# full_tds.net
KiCad netlist of a schematic drawn in EAGLE
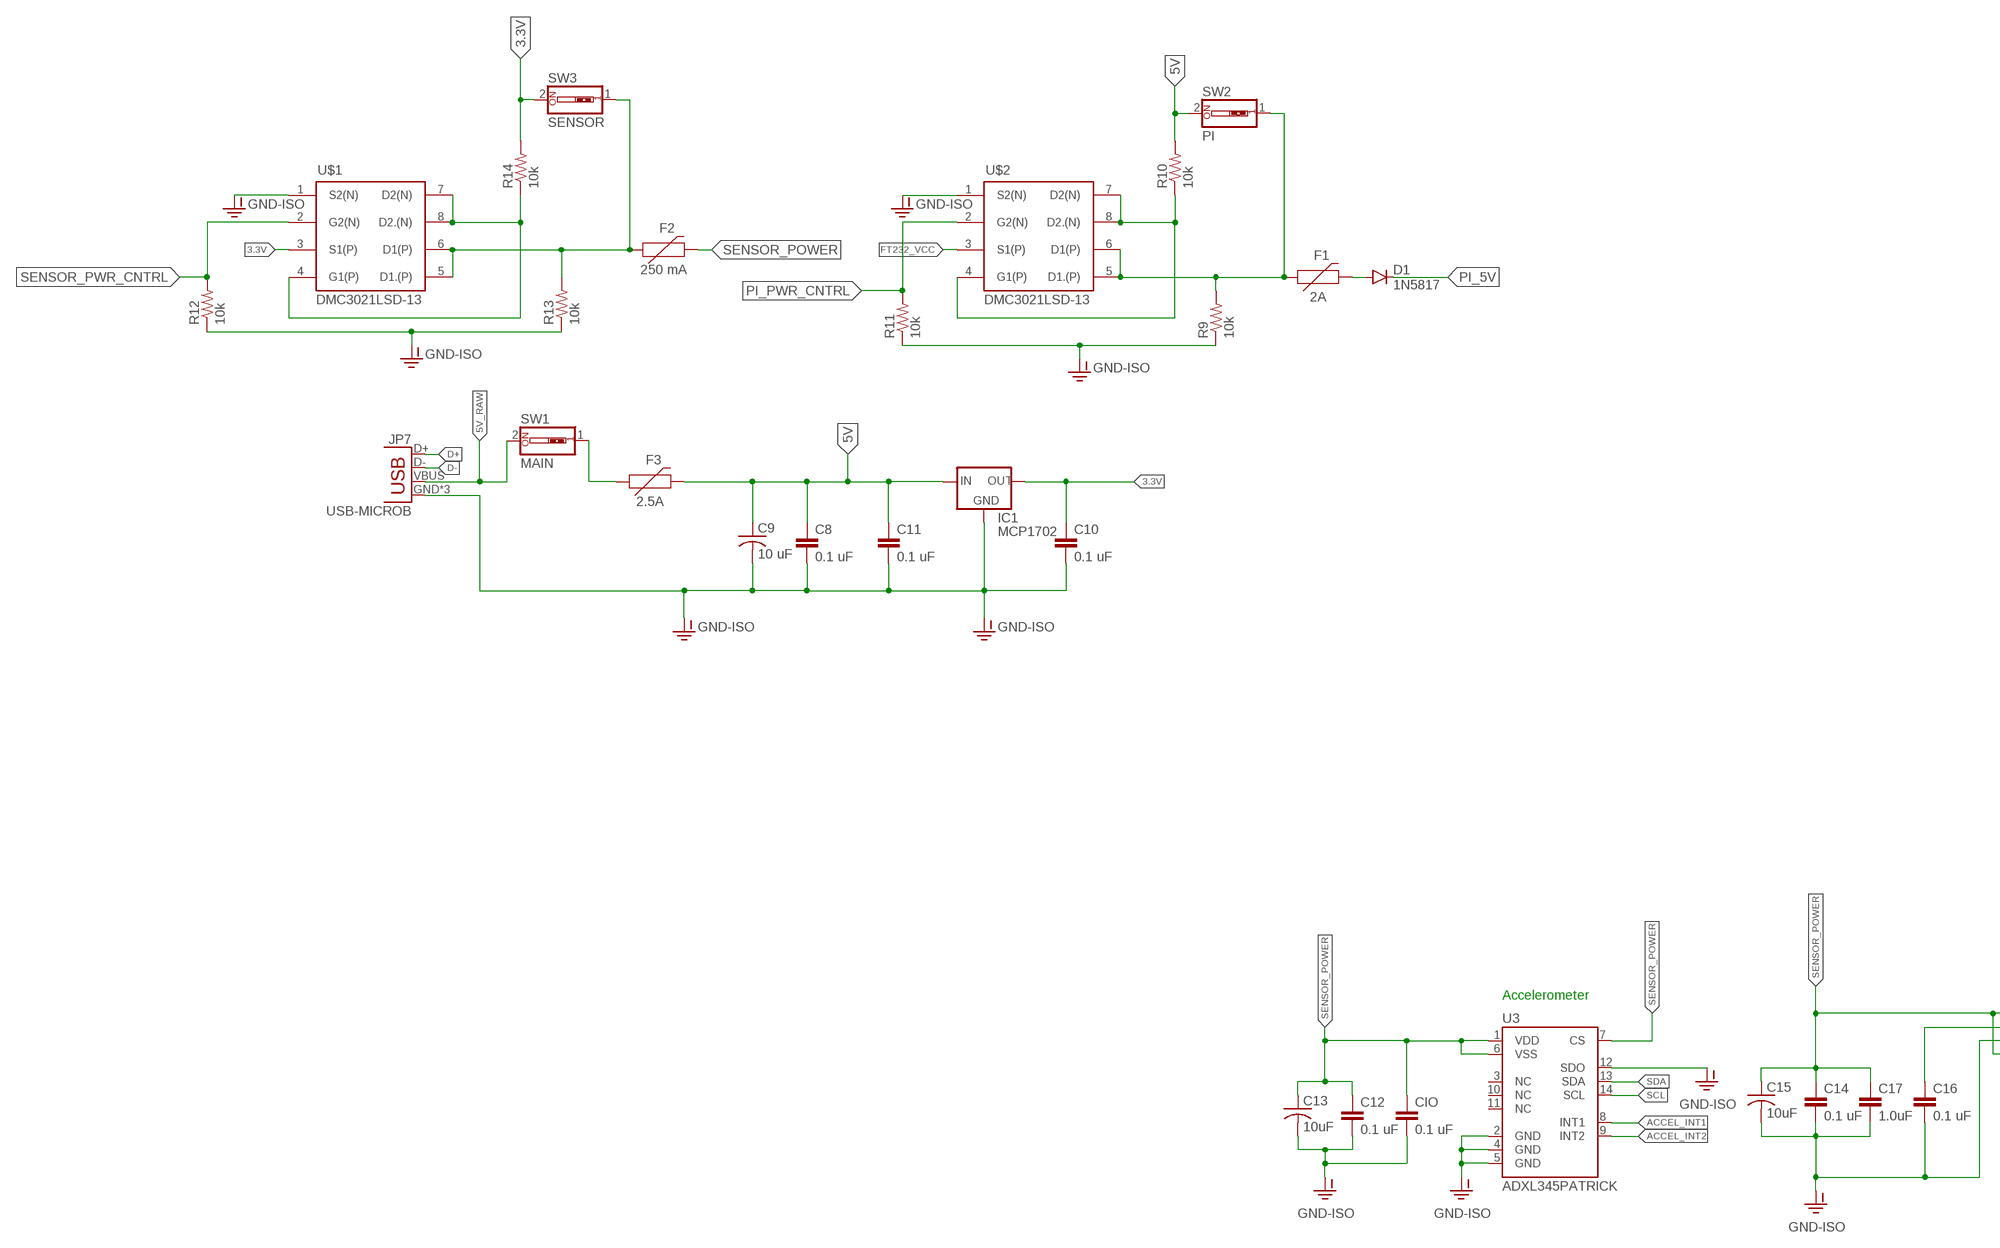
[diagram p0: schematic, sheet 1, part 1 of 2]
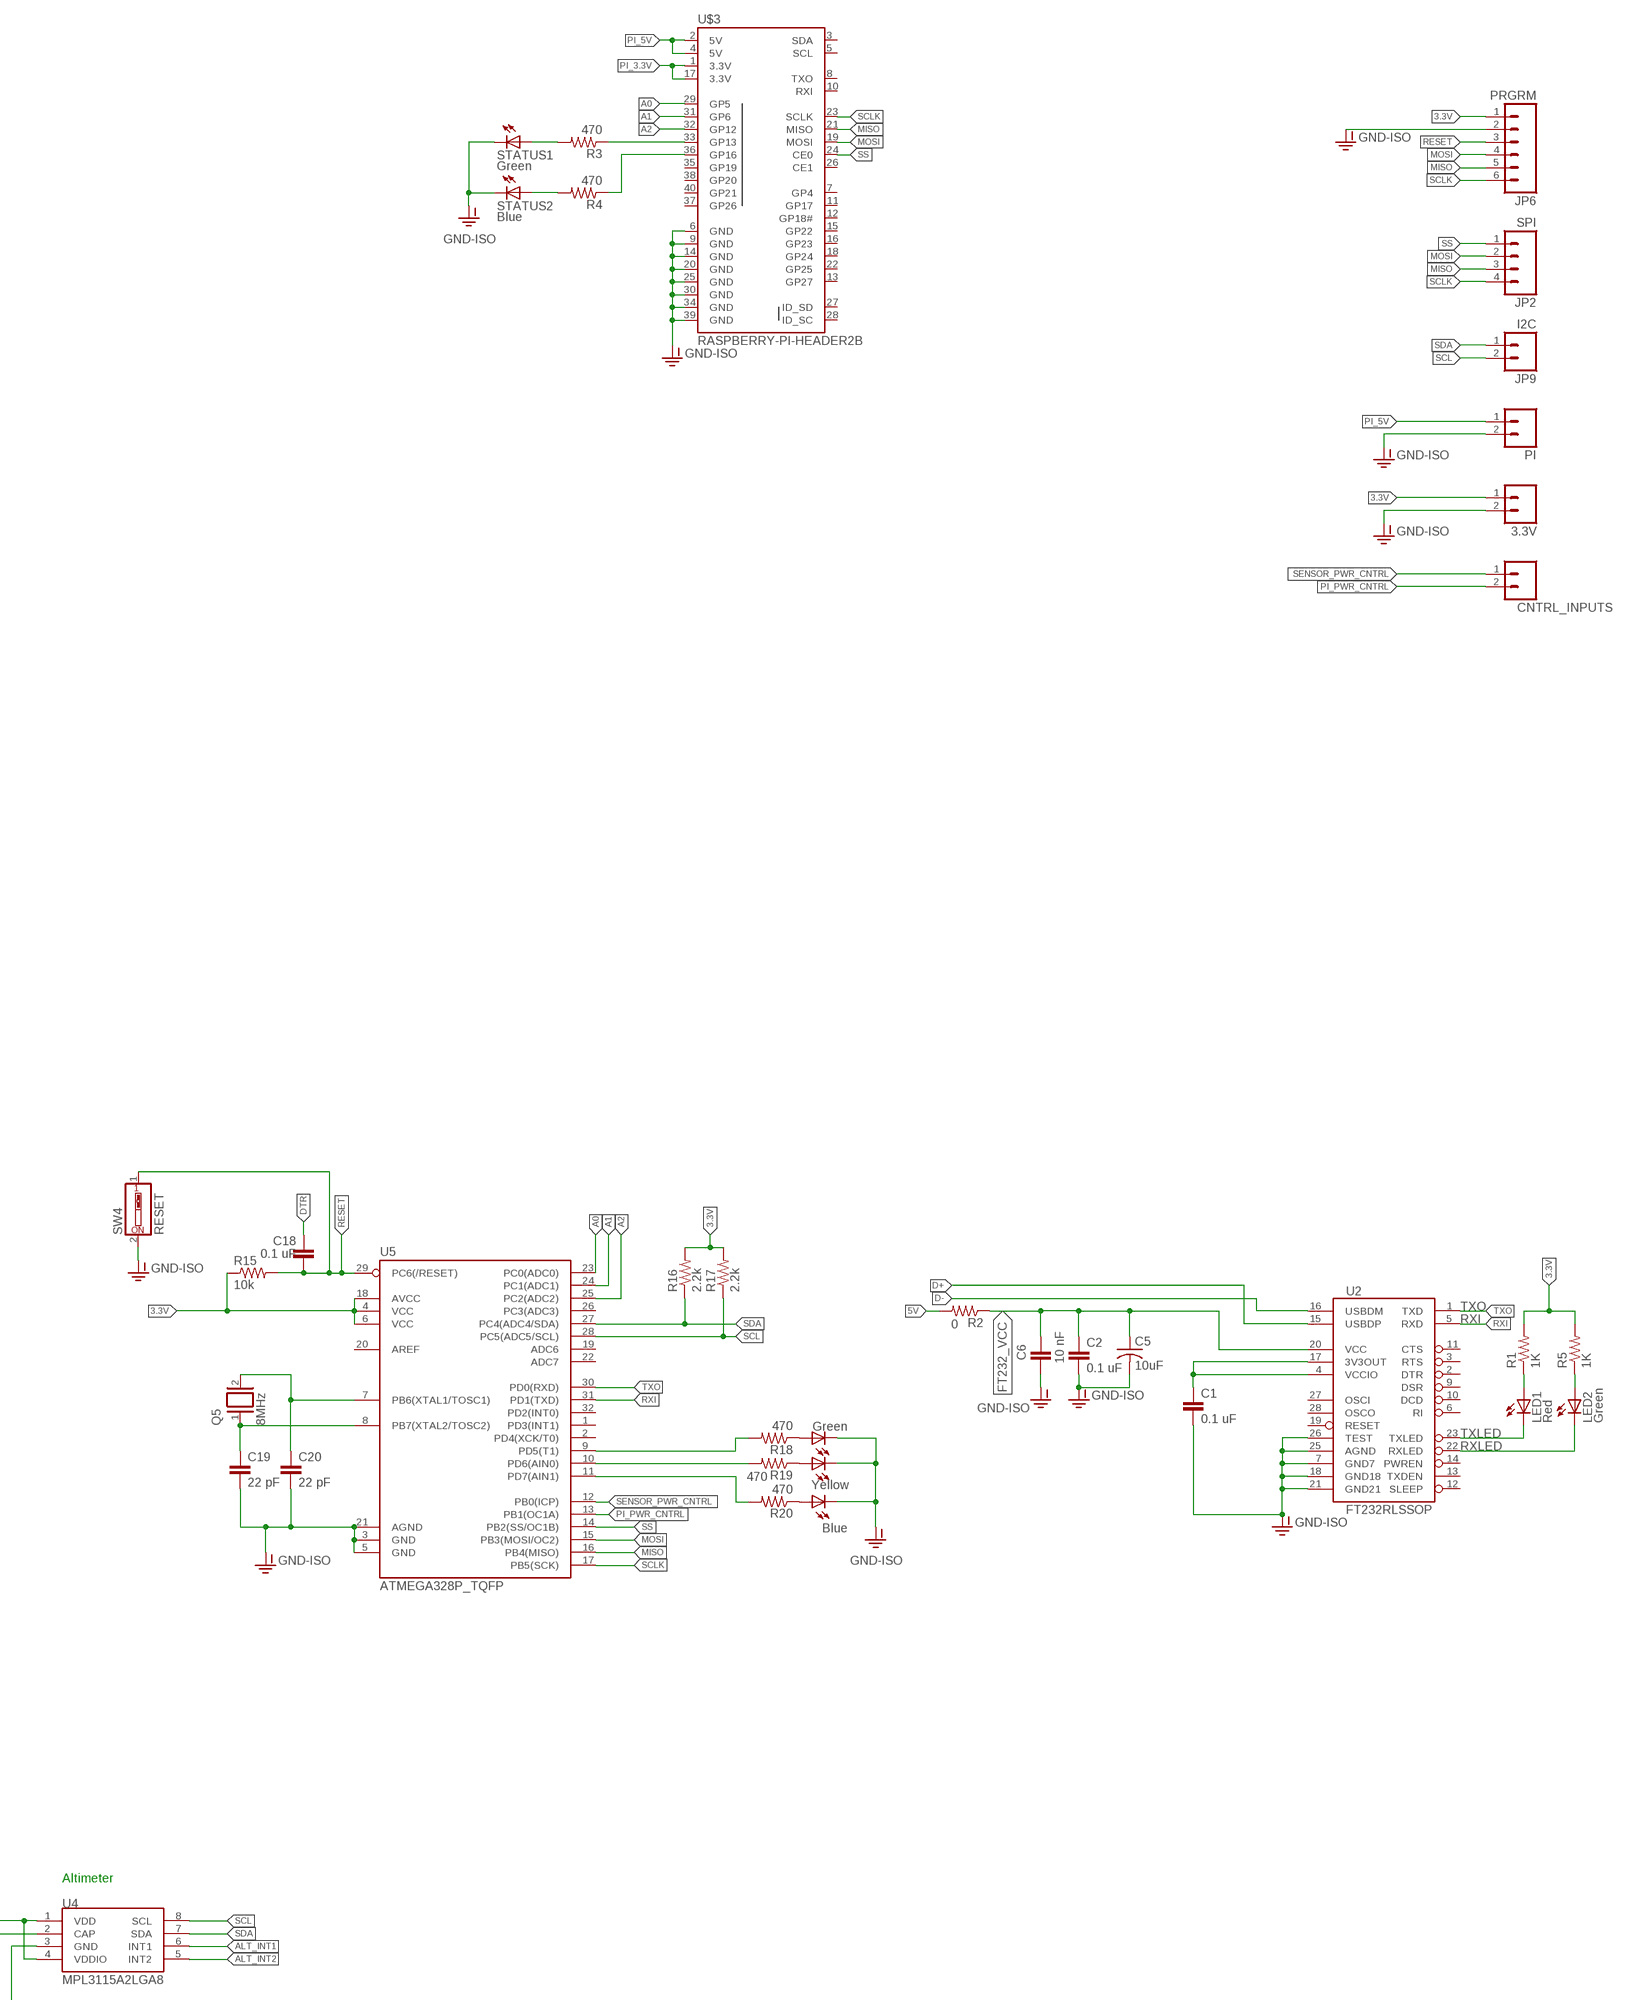
[diagram p1: schematic, sheet 1, part 2 of 2]

(export (version "E")
  (design (tool "Eeschema 10.0.6"))
  (components
    (comp (ref "3.3V")
      (value "M02PTH")
      (footprint "eagle-import:1X02")
      (libsource (lib "eagle-import") (part "M02PTH"))
    )
    (comp (ref "C1")
      (value "0.1 uF")
      (footprint "eagle-import:1206")
      (libsource (lib "eagle-import") (part "1.0UF-1206-50V-10%"))
    )
    (comp (ref "C2")
      (value "0.1 uF")
      (footprint "eagle-import:1206")
      (libsource (lib "eagle-import") (part "1.0UF-1206-50V-10%"))
    )
    (comp (ref "C5")
      (value "10uF")
      (footprint "eagle-import:C1206")
      (libsource (lib "eagle-import") (part "C-USC1206"))
    )
    (comp (ref "C6")
      (value "10 nF")
      (footprint "eagle-import:1206")
      (libsource (lib "eagle-import") (part "1.0UF-1206-50V-10%"))
    )
    (comp (ref "C8")
      (value "0.1 uF")
      (footprint "eagle-import:1206")
      (libsource (lib "eagle-import") (part "1.0UF-1206-50V-10%"))
    )
    (comp (ref "C9")
      (value "10 uF")
      (footprint "eagle-import:C1206")
      (libsource (lib "eagle-import") (part "C-USC1206"))
    )
    (comp (ref "C10")
      (value "0.1 uF")
      (footprint "eagle-import:1206")
      (libsource (lib "eagle-import") (part "1.0UF-1206-50V-10%"))
    )
    (comp (ref "C11")
      (value "0.1 uF")
      (footprint "eagle-import:1206")
      (libsource (lib "eagle-import") (part "1.0UF-1206-50V-10%"))
    )
    (comp (ref "C12")
      (value "0.1 uF")
      (footprint "eagle-import:1206")
      (libsource (lib "eagle-import") (part "1.0UF-1206-50V-10%"))
    )
    (comp (ref "C13")
      (value "10uF")
      (footprint "eagle-import:C1206")
      (libsource (lib "eagle-import") (part "C-USC1206"))
    )
    (comp (ref "C14")
      (value "0.1 uF")
      (footprint "eagle-import:1206")
      (libsource (lib "eagle-import") (part "1.0UF-1206-50V-10%"))
    )
    (comp (ref "C15")
      (value "10uF")
      (footprint "eagle-import:C1206")
      (libsource (lib "eagle-import") (part "C-USC1206"))
    )
    (comp (ref "C16")
      (value "0.1 uF")
      (footprint "eagle-import:1206")
      (libsource (lib "eagle-import") (part "1.0UF-1206-50V-10%"))
    )
    (comp (ref "C17")
      (value "1.0uF")
      (footprint "eagle-import:1206")
      (libsource (lib "eagle-import") (part "1.0UF-1206-50V-10%"))
    )
    (comp (ref "C18")
      (value "0.1 uF")
      (footprint "eagle-import:1206")
      (libsource (lib "eagle-import") (part "1.0UF-1206-50V-10%"))
    )
    (comp (ref "C19")
      (value "22 pF")
      (footprint "eagle-import:1206")
      (libsource (lib "eagle-import") (part "1.0UF-1206-50V-10%"))
    )
    (comp (ref "C20")
      (value "22 pF")
      (footprint "eagle-import:1206")
      (libsource (lib "eagle-import") (part "1.0UF-1206-50V-10%"))
    )
    (comp (ref "CIO")
      (value "0.1 uF")
      (footprint "eagle-import:1206")
      (libsource (lib "eagle-import") (part "1.0UF-1206-50V-10%"))
    )
    (comp (ref "CNTRL_INPUTS")
      (value "M02PTH")
      (footprint "eagle-import:1X02")
      (libsource (lib "eagle-import") (part "M02PTH"))
    )
    (comp (ref "D1")
      (value "1N5817")
      (footprint "eagle-import:DIODE-1N4001")
      (libsource (lib "eagle-import") (part "DIODEPTH"))
    )
    (comp (ref "F1")
      (value "2A")
      (footprint "eagle-import:1206")
      (libsource (lib "eagle-import") (part "PPTC_HALF-AMP"))
    )
    (comp (ref "F2")
      (value "250 mA")
      (footprint "eagle-import:1206")
      (libsource (lib "eagle-import") (part "PPTC_HALF-AMP"))
    )
    (comp (ref "F3")
      (value "2.5A")
      (footprint "eagle-import:1206")
      (libsource (lib "eagle-import") (part "PPTC_HALF-AMP"))
    )
    (comp (ref "IC1")
      (value "MCP1702")
      (footprint "eagle-import:TO92")
      (libsource (lib "eagle-import") (part "MCP1700TRI"))
    )
    (comp (ref "JP2")
      (value "SPI")
      (footprint "eagle-import:1X04")
      (libsource (lib "eagle-import") (part "M04PTH"))
    )
    (comp (ref "JP6")
      (value "PRGRM")
      (footprint "eagle-import:1X06")
      (libsource (lib "eagle-import") (part "M06SILK_FEMALE_PTH"))
    )
    (comp (ref "JP7")
      (value "USB-MICROB")
      (footprint "eagle-import:USB-MICROB")
      (libsource (lib "eagle-import") (part "USB-MICROB"))
    )
    (comp (ref "JP9")
      (value "I2C")
      (footprint "eagle-import:1X02")
      (libsource (lib "eagle-import") (part "M02PTH"))
    )
    (comp (ref "LED1")
      (value "Red")
      (footprint "eagle-import:CHIPLED_1206")
      (libsource (lib "eagle-import") (part "LEDCHIPLED_1206"))
    )
    (comp (ref "LED2")
      (value "Green")
      (footprint "eagle-import:CHIPLED_1206")
      (libsource (lib "eagle-import") (part "LEDCHIPLED_1206"))
    )
    (comp (ref "LED6")
      (value "Green")
      (footprint "eagle-import:CHIPLED_1206")
      (libsource (lib "eagle-import") (part "LEDCHIPLED_1206"))
    )
    (comp (ref "LED7")
      (value "Yellow")
      (footprint "eagle-import:CHIPLED_1206")
      (libsource (lib "eagle-import") (part "LEDCHIPLED_1206"))
    )
    (comp (ref "LED8")
      (value "Blue")
      (footprint "eagle-import:CHIPLED_1206")
      (libsource (lib "eagle-import") (part "LEDCHIPLED_1206"))
    )
    (comp (ref "PI")
      (value "M02PTH")
      (footprint "eagle-import:1X02")
      (libsource (lib "eagle-import") (part "M02PTH"))
    )
    (comp (ref "Q5")
      (value "8MHz")
      (footprint "eagle-import:QS")
      (libsource (lib "eagle-import") (part "XTAL/S"))
    )
    (comp (ref "R1")
      (value "1K")
      (footprint "eagle-import:1206")
      (libsource (lib "eagle-import") (part "SparkFun-Resistors_RESISTOR1206"))
    )
    (comp (ref "R2")
      (value "0")
      (footprint "eagle-import:1206")
      (libsource (lib "eagle-import") (part "SparkFun-Resistors_RESISTOR1206"))
    )
    (comp (ref "R3")
      (value "470")
      (footprint "eagle-import:1206")
      (libsource (lib "eagle-import") (part "RESISTOR1206"))
    )
    (comp (ref "R4")
      (value "470")
      (footprint "eagle-import:1206")
      (libsource (lib "eagle-import") (part "RESISTOR1206"))
    )
    (comp (ref "R5")
      (value "1K")
      (footprint "eagle-import:1206")
      (libsource (lib "eagle-import") (part "SparkFun-Resistors_RESISTOR1206"))
    )
    (comp (ref "R9")
      (value "10k")
      (footprint "eagle-import:R1206")
      (libsource (lib "eagle-import") (part "R-US_R1206"))
    )
    (comp (ref "R10")
      (value "10k")
      (footprint "eagle-import:R1206")
      (libsource (lib "eagle-import") (part "R-US_R1206"))
    )
    (comp (ref "R11")
      (value "10k")
      (footprint "eagle-import:R1206")
      (libsource (lib "eagle-import") (part "R-US_R1206"))
    )
    (comp (ref "R12")
      (value "10k")
      (footprint "eagle-import:R1206")
      (libsource (lib "eagle-import") (part "R-US_R1206"))
    )
    (comp (ref "R13")
      (value "10k")
      (footprint "eagle-import:R1206")
      (libsource (lib "eagle-import") (part "R-US_R1206"))
    )
    (comp (ref "R14")
      (value "10k")
      (footprint "eagle-import:R1206")
      (libsource (lib "eagle-import") (part "R-US_R1206"))
    )
    (comp (ref "R15")
      (value "10k")
      (footprint "eagle-import:1206")
      (libsource (lib "eagle-import") (part "RESISTOR1206"))
    )
    (comp (ref "R16")
      (value "2.2k")
      (footprint "eagle-import:1206")
      (libsource (lib "eagle-import") (part "RESISTOR1206"))
    )
    (comp (ref "R17")
      (value "2.2k")
      (footprint "eagle-import:1206")
      (libsource (lib "eagle-import") (part "RESISTOR1206"))
    )
    (comp (ref "R18")
      (value "470")
      (footprint "eagle-import:1206")
      (libsource (lib "eagle-import") (part "RESISTOR1206"))
    )
    (comp (ref "R19")
      (value "470")
      (footprint "eagle-import:1206")
      (libsource (lib "eagle-import") (part "RESISTOR1206"))
    )
    (comp (ref "R20")
      (value "470")
      (footprint "eagle-import:1206")
      (libsource (lib "eagle-import") (part "RESISTOR1206"))
    )
    (comp (ref "STATUS1")
      (value "Green")
      (footprint "eagle-import:CHIPLED_1206")
      (libsource (lib "eagle-import") (part "LEDCHIPLED_1206"))
    )
    (comp (ref "STATUS2")
      (value "Blue")
      (footprint "eagle-import:CHIPLED_1206")
      (libsource (lib "eagle-import") (part "LEDCHIPLED_1206"))
    )
    (comp (ref "SW1")
      (value "MAIN")
      (footprint "eagle-import:EDG-01")
      (libsource (lib "eagle-import") (part "SW_DIP-1"))
    )
    (comp (ref "SW2")
      (value "PI")
      (footprint "eagle-import:EDG-01")
      (libsource (lib "eagle-import") (part "SW_DIP-1"))
    )
    (comp (ref "SW3")
      (value "SENSOR")
      (footprint "eagle-import:EDG-01")
      (libsource (lib "eagle-import") (part "SW_DIP-1"))
    )
    (comp (ref "SW4")
      (value "RESET")
      (footprint "eagle-import:EDG-01")
      (libsource (lib "eagle-import") (part "SW_DIP-1"))
    )
    (comp (ref "U$1")
      (value "DMC3021LSD-13")
      (footprint "eagle-import:SOIC-8")
      (libsource (lib "eagle-import") (part "DMC3021LSD-13"))
    )
    (comp (ref "U$2")
      (value "DMC3021LSD-13")
      (footprint "eagle-import:SOIC-8")
      (libsource (lib "eagle-import") (part "DMC3021LSD-13"))
    )
    (comp (ref "U$3")
      (value "RASPBERRY-PI-HEADER2B")
      (footprint "eagle-import:2X20-NOSILK")
      (libsource (lib "eagle-import") (part "RASPBERRY-PI-HEADER2B"))
    )
    (comp (ref "U2")
      (value "FT232RLSSOP")
      (footprint "eagle-import:SSOP28DB")
      (libsource (lib "eagle-import") (part "FT232RLSSOP"))
    )
    (comp (ref "U3")
      (value "ADXL345PATRICK")
      (footprint "eagle-import:LGA14_1_1_PATRICK")
      (libsource (lib "eagle-import") (part "ADXL345PATRICK"))
    )
    (comp (ref "U4")
      (value "MPL3115A2LGA8")
      (footprint "eagle-import:LGA8")
      (libsource (lib "eagle-import") (part "MPL3115A2LGA8"))
    )
    (comp (ref "U5")
      (value "ATMEGA328P_TQFP")
      (footprint "eagle-import:TQFP32-08")
      (libsource (lib "eagle-import") (part "ATMEGA328P_TQFP"))
    )
  )
  (nets
    (net (code "1") (name "/RXLED") (class "Default")
      (node (ref "LED2") (pin "C") (pinfunction "C_C") (pintype "passive"))
      (node (ref "U2") (pin "22") (pinfunction "RXLED_22") (pintype "input"))
    )
    (net (code "2") (name "/TXLED") (class "Default")
      (node (ref "LED1") (pin "C") (pinfunction "C_C") (pintype "passive"))
      (node (ref "U2") (pin "23") (pinfunction "TXLED_23") (pintype "input"))
    )
    (net (code "3") (name "3.3V") (class "Default")
      (node (ref "3.3V") (pin "1") (pinfunction "1_1") (pintype "passive"))
      (node (ref "C10") (pin "1") (pinfunction "1_1") (pintype "passive"))
      (node (ref "IC1") (pin "3") (pinfunction "OUT_3") (pintype "passive"))
      (node (ref "JP6") (pin "1") (pinfunction "1_1") (pintype "passive"))
      (node (ref "R1") (pin "2") (pinfunction "2_2") (pintype "passive"))
      (node (ref "R14") (pin "2") (pinfunction "2_2") (pintype "passive"))
      (node (ref "R15") (pin "1") (pinfunction "1_1") (pintype "passive"))
      (node (ref "R16") (pin "2") (pinfunction "2_2") (pintype "passive"))
      (node (ref "R17") (pin "2") (pinfunction "2_2") (pintype "passive"))
      (node (ref "R5") (pin "2") (pinfunction "2_2") (pintype "passive"))
      (node (ref "SW3") (pin "2") (pinfunction "2_2") (pintype "passive"))
      (node (ref "U$1") (pin "3") (pinfunction "S1(P)_3") (pintype "bidirectional"))
      (node (ref "U5") (pin "18") (pinfunction "AVCC_18") (pintype "bidirectional"))
      (node (ref "U5") (pin "4") (pinfunction "VCC_4") (pintype "bidirectional"))
      (node (ref "U5") (pin "6") (pinfunction "VCC_6") (pintype "bidirectional"))
    )
    (net (code "4") (name "5V") (class "Default")
      (node (ref "C11") (pin "1") (pinfunction "1_1") (pintype "passive"))
      (node (ref "C8") (pin "1") (pinfunction "1_1") (pintype "passive"))
      (node (ref "C9") (pin "1") (pinfunction "1_1") (pintype "passive"))
      (node (ref "F3") (pin "2") (pinfunction "2_2") (pintype "bidirectional"))
      (node (ref "IC1") (pin "2") (pinfunction "IN_2") (pintype "input"))
      (node (ref "R10") (pin "2") (pinfunction "2_2") (pintype "passive"))
      (node (ref "R2") (pin "2") (pinfunction "2_2") (pintype "passive"))
      (node (ref "SW2") (pin "2") (pinfunction "2_2") (pintype "passive"))
    )
    (net (code "5") (name "5V_RAW") (class "Default")
      (node (ref "JP7") (pin "VBUS") (pinfunction "VBUS_VBUS") (pintype "bidirectional"))
      (node (ref "SW1") (pin "2") (pinfunction "2_2") (pintype "passive"))
    )
    (net (code "6") (name "A0") (class "Default")
      (node (ref "U$3") (pin "29") (pinfunction "GP5_29") (pintype "bidirectional"))
      (node (ref "U5") (pin "23") (pinfunction "PC0(ADC0)_23") (pintype "bidirectional"))
    )
    (net (code "7") (name "A1") (class "Default")
      (node (ref "U$3") (pin "31") (pinfunction "GP6_31") (pintype "bidirectional"))
      (node (ref "U5") (pin "24") (pinfunction "PC1(ADC1)_24") (pintype "bidirectional"))
    )
    (net (code "8") (name "A2") (class "Default")
      (node (ref "U$3") (pin "32") (pinfunction "GP12_32") (pintype "bidirectional"))
      (node (ref "U5") (pin "25") (pinfunction "PC2(ADC2)_25") (pintype "bidirectional"))
    )
    (net (code "9") (name "ACCEL_INT1") (class "Default")
      (node (ref "U3") (pin "8") (pinfunction "INT1_8") (pintype "bidirectional"))
    )
    (net (code "10") (name "ACCEL_INT2") (class "Default")
      (node (ref "U3") (pin "9") (pinfunction "INT2_9") (pintype "bidirectional"))
    )
    (net (code "11") (name "ALT_INT1") (class "Default")
      (node (ref "U4") (pin "6") (pinfunction "INT1_6") (pintype "bidirectional"))
    )
    (net (code "12") (name "ALT_INT2") (class "Default")
      (node (ref "U4") (pin "5") (pinfunction "INT2_5") (pintype "bidirectional"))
    )
    (net (code "13") (name "D+") (class "Default")
      (node (ref "JP7") (pin "D+") (pinfunction "D+_D+") (pintype "bidirectional"))
      (node (ref "U2") (pin "15") (pinfunction "USBDP_15") (pintype "bidirectional"))
    )
    (net (code "14") (name "D-") (class "Default")
      (node (ref "JP7") (pin "D-") (pinfunction "D-_D-") (pintype "bidirectional"))
      (node (ref "U2") (pin "16") (pinfunction "USBDM_16") (pintype "bidirectional"))
    )
    (net (code "15") (name "DTR") (class "Default")
      (node (ref "C18") (pin "1") (pinfunction "1_1") (pintype "passive"))
    )
    (net (code "16") (name "FT232_VCC") (class "Default")
      (node (ref "C2") (pin "1") (pinfunction "1_1") (pintype "passive"))
      (node (ref "C5") (pin "1") (pinfunction "1_1") (pintype "passive"))
      (node (ref "C6") (pin "2") (pinfunction "2_2") (pintype "passive"))
      (node (ref "R2") (pin "1") (pinfunction "1_1") (pintype "passive"))
      (node (ref "U$2") (pin "3") (pinfunction "S1(P)_3") (pintype "bidirectional"))
      (node (ref "U2") (pin "20") (pinfunction "VCC_20") (pintype "power_in"))
    )
    (net (code "17") (name "GND-ISO") (class "Default")
      (node (ref "3.3V") (pin "2") (pinfunction "2_2") (pintype "passive"))
      (node (ref "C1") (pin "2") (pinfunction "2_2") (pintype "passive"))
      (node (ref "C10") (pin "2") (pinfunction "2_2") (pintype "passive"))
      (node (ref "C11") (pin "2") (pinfunction "2_2") (pintype "passive"))
      (node (ref "C12") (pin "2") (pinfunction "2_2") (pintype "passive"))
      (node (ref "C13") (pin "2") (pinfunction "2_2") (pintype "passive"))
      (node (ref "C14") (pin "2") (pinfunction "2_2") (pintype "passive"))
      (node (ref "C15") (pin "2") (pinfunction "2_2") (pintype "passive"))
      (node (ref "C16") (pin "2") (pinfunction "2_2") (pintype "passive"))
      (node (ref "C17") (pin "2") (pinfunction "2_2") (pintype "passive"))
      (node (ref "C19") (pin "2") (pinfunction "2_2") (pintype "passive"))
      (node (ref "C2") (pin "2") (pinfunction "2_2") (pintype "passive"))
      (node (ref "C20") (pin "2") (pinfunction "2_2") (pintype "passive"))
      (node (ref "C5") (pin "2") (pinfunction "2_2") (pintype "passive"))
      (node (ref "C6") (pin "1") (pinfunction "1_1") (pintype "passive"))
      (node (ref "C8") (pin "2") (pinfunction "2_2") (pintype "passive"))
      (node (ref "C9") (pin "2") (pinfunction "2_2") (pintype "passive"))
      (node (ref "CIO") (pin "2") (pinfunction "2_2") (pintype "passive"))
      (node (ref "IC1") (pin "1") (pinfunction "GND_1") (pintype "input"))
      (node (ref "JP6") (pin "2") (pinfunction "2_2") (pintype "passive"))
      (node (ref "JP7") (pin "GND") (pinfunction "GND_GND") (pintype "bidirectional"))
      (node (ref "JP7") (pin "MT1") (pinfunction "GND_MT1") (pintype "bidirectional"))
      (node (ref "JP7") (pin "MT2") (pinfunction "GND_MT2") (pintype "bidirectional"))
      (node (ref "LED6") (pin "C") (pinfunction "C_C") (pintype "passive"))
      (node (ref "LED7") (pin "C") (pinfunction "C_C") (pintype "passive"))
      (node (ref "LED8") (pin "C") (pinfunction "C_C") (pintype "passive"))
      (node (ref "PI") (pin "2") (pinfunction "2_2") (pintype "passive"))
      (node (ref "R11") (pin "1") (pinfunction "1_1") (pintype "passive"))
      (node (ref "R12") (pin "1") (pinfunction "1_1") (pintype "passive"))
      (node (ref "R13") (pin "1") (pinfunction "1_1") (pintype "passive"))
      (node (ref "R9") (pin "1") (pinfunction "1_1") (pintype "passive"))
      (node (ref "STATUS1") (pin "C") (pinfunction "C_C") (pintype "passive"))
      (node (ref "STATUS2") (pin "C") (pinfunction "C_C") (pintype "passive"))
      (node (ref "SW4") (pin "2") (pinfunction "2_2") (pintype "passive"))
      (node (ref "U$1") (pin "1") (pinfunction "S2(N)_1") (pintype "bidirectional"))
      (node (ref "U$2") (pin "1") (pinfunction "S2(N)_1") (pintype "bidirectional"))
      (node (ref "U$3") (pin "14") (pinfunction "GND_14") (pintype "power_in"))
      (node (ref "U$3") (pin "20") (pinfunction "GND_20") (pintype "power_in"))
      (node (ref "U$3") (pin "25") (pinfunction "GND_25") (pintype "power_in"))
      (node (ref "U$3") (pin "30") (pinfunction "GND_30") (pintype "power_in"))
      (node (ref "U$3") (pin "34") (pinfunction "GND_34") (pintype "power_in"))
      (node (ref "U$3") (pin "39") (pinfunction "GND_39") (pintype "power_in"))
      (node (ref "U$3") (pin "6") (pinfunction "GND_6") (pintype "power_in"))
      (node (ref "U$3") (pin "9") (pinfunction "GND_9") (pintype "power_in"))
      (node (ref "U2") (pin "18") (pinfunction "GND18_18") (pintype "power_in"))
      (node (ref "U2") (pin "21") (pinfunction "GND21_21") (pintype "power_in"))
      (node (ref "U2") (pin "25") (pinfunction "AGND_25") (pintype "power_in"))
      (node (ref "U2") (pin "26") (pinfunction "TEST_26") (pintype "input"))
      (node (ref "U2") (pin "7") (pinfunction "GND7_7") (pintype "power_in"))
      (node (ref "U3") (pin "12") (pinfunction "SDO_12") (pintype "bidirectional"))
      (node (ref "U3") (pin "2") (pinfunction "GND_2") (pintype "bidirectional"))
      (node (ref "U3") (pin "4") (pinfunction "GND_4") (pintype "bidirectional"))
      (node (ref "U3") (pin "5") (pinfunction "GND_5") (pintype "bidirectional"))
      (node (ref "U4") (pin "3") (pinfunction "GND_3") (pintype "bidirectional"))
      (node (ref "U5") (pin "21") (pinfunction "AGND_21") (pintype "bidirectional"))
      (node (ref "U5") (pin "3") (pinfunction "GND_3") (pintype "bidirectional"))
      (node (ref "U5") (pin "5") (pinfunction "GND_5") (pintype "bidirectional"))
    )
    (net (code "18") (name "MISO") (class "Default")
      (node (ref "JP2") (pin "3") (pinfunction "3_3") (pintype "passive"))
      (node (ref "JP6") (pin "5") (pinfunction "5_5") (pintype "passive"))
      (node (ref "U$3") (pin "21") (pinfunction "MISO_21") (pintype "input"))
      (node (ref "U5") (pin "16") (pinfunction "PB4(MISO)_16") (pintype "bidirectional"))
    )
    (net (code "19") (name "MOSI") (class "Default")
      (node (ref "JP2") (pin "2") (pinfunction "2_2") (pintype "passive"))
      (node (ref "JP6") (pin "4") (pinfunction "4_4") (pintype "passive"))
      (node (ref "U$3") (pin "19") (pinfunction "MOSI_19") (pintype "output"))
      (node (ref "U5") (pin "15") (pinfunction "PB3(MOSI/OC2)_15") (pintype "bidirectional"))
    )
    (net (code "20") (name "Net-(D1-PadA)") (class "Default")
      (node (ref "D1") (pin "A") (pinfunction "A_A") (pintype "passive"))
      (node (ref "F1") (pin "2") (pinfunction "2_2") (pintype "bidirectional"))
    )
    (net (code "21") (name "Net-(F3-Pad1)") (class "Default")
      (node (ref "F3") (pin "1") (pinfunction "1_1") (pintype "bidirectional"))
      (node (ref "SW1") (pin "1") (pinfunction "1_1") (pintype "passive"))
    )
    (net (code "22") (name "Net-(LED1-PadA)") (class "Default")
      (node (ref "LED1") (pin "A") (pinfunction "A_A") (pintype "passive"))
      (node (ref "R1") (pin "1") (pinfunction "1_1") (pintype "passive"))
    )
    (net (code "23") (name "Net-(LED2-PadA)") (class "Default")
      (node (ref "LED2") (pin "A") (pinfunction "A_A") (pintype "passive"))
      (node (ref "R5") (pin "1") (pinfunction "1_1") (pintype "passive"))
    )
    (net (code "24") (name "Net-(LED6-PadA)") (class "Default")
      (node (ref "LED6") (pin "A") (pinfunction "A_A") (pintype "passive"))
      (node (ref "R18") (pin "1") (pinfunction "1_1") (pintype "passive"))
    )
    (net (code "25") (name "Net-(LED7-PadA)") (class "Default")
      (node (ref "LED7") (pin "A") (pinfunction "A_A") (pintype "passive"))
      (node (ref "R19") (pin "1") (pinfunction "1_1") (pintype "passive"))
    )
    (net (code "26") (name "Net-(LED8-PadA)") (class "Default")
      (node (ref "LED8") (pin "A") (pinfunction "A_A") (pintype "passive"))
      (node (ref "R20") (pin "1") (pinfunction "1_1") (pintype "passive"))
    )
    (net (code "27") (name "Net-(R3-Pad2)") (class "Default")
      (node (ref "R3") (pin "2") (pinfunction "2_2") (pintype "passive"))
      (node (ref "STATUS1") (pin "A") (pinfunction "A_A") (pintype "passive"))
    )
    (net (code "28") (name "Net-(R4-Pad2)") (class "Default")
      (node (ref "R4") (pin "2") (pinfunction "2_2") (pintype "passive"))
      (node (ref "STATUS2") (pin "A") (pinfunction "A_A") (pintype "passive"))
    )
    (net (code "29") (name "Net-(U$1-D1(P))") (class "Default")
      (node (ref "F2") (pin "1") (pinfunction "1_1") (pintype "bidirectional"))
      (node (ref "R13") (pin "2") (pinfunction "2_2") (pintype "passive"))
      (node (ref "SW3") (pin "1") (pinfunction "1_1") (pintype "passive"))
      (node (ref "U$1") (pin "5") (pinfunction "D1.(P)_5") (pintype "bidirectional"))
      (node (ref "U$1") (pin "6") (pinfunction "D1(P)_6") (pintype "bidirectional"))
    )
    (net (code "30") (name "Net-(U$1-D2(N))") (class "Default")
      (node (ref "R14") (pin "1") (pinfunction "1_1") (pintype "passive"))
      (node (ref "U$1") (pin "4") (pinfunction "G1(P)_4") (pintype "bidirectional"))
      (node (ref "U$1") (pin "7") (pinfunction "D2(N)_7") (pintype "bidirectional"))
      (node (ref "U$1") (pin "8") (pinfunction "D2.(N)_8") (pintype "bidirectional"))
    )
    (net (code "31") (name "Net-(U$2-D1(P))") (class "Default")
      (node (ref "F1") (pin "1") (pinfunction "1_1") (pintype "bidirectional"))
      (node (ref "R9") (pin "2") (pinfunction "2_2") (pintype "passive"))
      (node (ref "SW2") (pin "1") (pinfunction "1_1") (pintype "passive"))
      (node (ref "U$2") (pin "5") (pinfunction "D1.(P)_5") (pintype "bidirectional"))
      (node (ref "U$2") (pin "6") (pinfunction "D1(P)_6") (pintype "bidirectional"))
    )
    (net (code "32") (name "Net-(U$2-D2(N))") (class "Default")
      (node (ref "R10") (pin "1") (pinfunction "1_1") (pintype "passive"))
      (node (ref "U$2") (pin "4") (pinfunction "G1(P)_4") (pintype "bidirectional"))
      (node (ref "U$2") (pin "7") (pinfunction "D2(N)_7") (pintype "bidirectional"))
      (node (ref "U$2") (pin "8") (pinfunction "D2.(N)_8") (pintype "bidirectional"))
    )
    (net (code "33") (name "Net-(U$3-GP13)") (class "Default")
      (node (ref "R3") (pin "1") (pinfunction "1_1") (pintype "passive"))
      (node (ref "U$3") (pin "33") (pinfunction "GP13_33") (pintype "bidirectional"))
    )
    (net (code "34") (name "Net-(U$3-GP16)") (class "Default")
      (node (ref "R4") (pin "1") (pinfunction "1_1") (pintype "passive"))
      (node (ref "U$3") (pin "36") (pinfunction "GP16_36") (pintype "bidirectional"))
    )
    (net (code "35") (name "Net-(U2-3V3OUT)") (class "Default")
      (node (ref "C1") (pin "1") (pinfunction "1_1") (pintype "passive"))
      (node (ref "U2") (pin "17") (pinfunction "3V3OUT_17") (pintype "output"))
      (node (ref "U2") (pin "4") (pinfunction "VCCIO_4") (pintype "power_in"))
    )
    (net (code "36") (name "Net-(U4-CAP)") (class "Default")
      (node (ref "C16") (pin "1") (pinfunction "1_1") (pintype "passive"))
      (node (ref "U4") (pin "2") (pinfunction "CAP_2") (pintype "bidirectional"))
    )
    (net (code "37") (name "Net-(U5-PB6(XTAL1{slash}TOSC1))") (class "Default")
      (node (ref "C20") (pin "1") (pinfunction "1_1") (pintype "passive"))
      (node (ref "Q5") (pin "2") (pinfunction "2_2") (pintype "passive"))
      (node (ref "U5") (pin "7") (pinfunction "PB6(XTAL1/TOSC1)_7") (pintype "bidirectional"))
    )
    (net (code "38") (name "Net-(U5-PB7(XTAL2{slash}TOSC2))") (class "Default")
      (node (ref "C19") (pin "1") (pinfunction "1_1") (pintype "passive"))
      (node (ref "Q5") (pin "1") (pinfunction "1_1") (pintype "passive"))
      (node (ref "U5") (pin "8") (pinfunction "PB7(XTAL2/TOSC2)_8") (pintype "bidirectional"))
    )
    (net (code "39") (name "Net-(U5-PD5(T1))") (class "Default")
      (node (ref "R18") (pin "2") (pinfunction "2_2") (pintype "passive"))
      (node (ref "U5") (pin "9") (pinfunction "PD5(T1)_9") (pintype "bidirectional"))
    )
    (net (code "40") (name "Net-(U5-PD6(AIN0))") (class "Default")
      (node (ref "R19") (pin "2") (pinfunction "2_2") (pintype "passive"))
      (node (ref "U5") (pin "10") (pinfunction "PD6(AIN0)_10") (pintype "bidirectional"))
    )
    (net (code "41") (name "Net-(U5-PD7(AIN1))") (class "Default")
      (node (ref "R20") (pin "2") (pinfunction "2_2") (pintype "passive"))
      (node (ref "U5") (pin "11") (pinfunction "PD7(AIN1)_11") (pintype "bidirectional"))
    )
    (net (code "42") (name "PI_3.3V") (class "Default")
      (node (ref "U$3") (pin "1") (pinfunction "3.3V_1") (pintype "power_in"))
      (node (ref "U$3") (pin "17") (pinfunction "3.3V_17") (pintype "power_in"))
    )
    (net (code "43") (name "PI_5V") (class "Default")
      (node (ref "D1") (pin "C") (pinfunction "C_C") (pintype "passive"))
      (node (ref "PI") (pin "1") (pinfunction "1_1") (pintype "passive"))
      (node (ref "U$3") (pin "2") (pinfunction "5V_2") (pintype "power_in"))
      (node (ref "U$3") (pin "4") (pinfunction "5V_4") (pintype "power_in"))
    )
    (net (code "44") (name "PI_PWR_CNTRL") (class "Default")
      (node (ref "CNTRL_INPUTS") (pin "2") (pinfunction "2_2") (pintype "passive"))
      (node (ref "R11") (pin "2") (pinfunction "2_2") (pintype "passive"))
      (node (ref "U$2") (pin "2") (pinfunction "G2(N)_2") (pintype "bidirectional"))
      (node (ref "U5") (pin "13") (pinfunction "PB1(OC1A)_13") (pintype "bidirectional"))
    )
    (net (code "45") (name "RESET") (class "Default")
      (node (ref "C18") (pin "2") (pinfunction "2_2") (pintype "passive"))
      (node (ref "JP6") (pin "3") (pinfunction "3_3") (pintype "passive"))
      (node (ref "R15") (pin "2") (pinfunction "2_2") (pintype "passive"))
      (node (ref "SW4") (pin "1") (pinfunction "1_1") (pintype "passive"))
      (node (ref "U5") (pin "29") (pinfunction "PC6(/RESET)_29") (pintype "bidirectional"))
    )
    (net (code "46") (name "RXI") (class "Default")
      (node (ref "U2") (pin "5") (pinfunction "RXD_5") (pintype "input"))
      (node (ref "U5") (pin "31") (pinfunction "PD1(TXD)_31") (pintype "bidirectional"))
    )
    (net (code "47") (name "SCL") (class "Default")
      (node (ref "JP9") (pin "2") (pinfunction "2_2") (pintype "passive"))
      (node (ref "R17") (pin "1") (pinfunction "1_1") (pintype "passive"))
      (node (ref "U3") (pin "14") (pinfunction "SCL_14") (pintype "bidirectional"))
      (node (ref "U4") (pin "8") (pinfunction "SCL_8") (pintype "bidirectional"))
      (node (ref "U5") (pin "28") (pinfunction "PC5(ADC5/SCL)_28") (pintype "bidirectional"))
    )
    (net (code "48") (name "SCLK") (class "Default")
      (node (ref "JP2") (pin "4") (pinfunction "4_4") (pintype "passive"))
      (node (ref "JP6") (pin "6") (pinfunction "6_6") (pintype "passive"))
      (node (ref "U$3") (pin "23") (pinfunction "SCLK_23") (pintype "output"))
      (node (ref "U5") (pin "17") (pinfunction "PB5(SCK)_17") (pintype "bidirectional"))
    )
    (net (code "49") (name "SDA") (class "Default")
      (node (ref "JP9") (pin "1") (pinfunction "1_1") (pintype "passive"))
      (node (ref "R16") (pin "1") (pinfunction "1_1") (pintype "passive"))
      (node (ref "U3") (pin "13") (pinfunction "SDA_13") (pintype "bidirectional"))
      (node (ref "U4") (pin "7") (pinfunction "SDA_7") (pintype "bidirectional"))
      (node (ref "U5") (pin "27") (pinfunction "PC4(ADC4/SDA)_27") (pintype "bidirectional"))
    )
    (net (code "50") (name "SENSOR_POWER") (class "Default")
      (node (ref "C12") (pin "1") (pinfunction "1_1") (pintype "passive"))
      (node (ref "C13") (pin "1") (pinfunction "1_1") (pintype "passive"))
      (node (ref "C14") (pin "1") (pinfunction "1_1") (pintype "passive"))
      (node (ref "C15") (pin "1") (pinfunction "1_1") (pintype "passive"))
      (node (ref "C17") (pin "1") (pinfunction "1_1") (pintype "passive"))
      (node (ref "CIO") (pin "1") (pinfunction "1_1") (pintype "passive"))
      (node (ref "F2") (pin "2") (pinfunction "2_2") (pintype "bidirectional"))
      (node (ref "U3") (pin "1") (pinfunction "VDD_1") (pintype "bidirectional"))
      (node (ref "U3") (pin "6") (pinfunction "VSS_6") (pintype "bidirectional"))
      (node (ref "U3") (pin "7") (pinfunction "CS_7") (pintype "bidirectional"))
      (node (ref "U4") (pin "1") (pinfunction "VDD_1") (pintype "bidirectional"))
      (node (ref "U4") (pin "4") (pinfunction "VDDIO_4") (pintype "bidirectional"))
    )
    (net (code "51") (name "SENSOR_PWR_CNTRL") (class "Default")
      (node (ref "CNTRL_INPUTS") (pin "1") (pinfunction "1_1") (pintype "passive"))
      (node (ref "R12") (pin "2") (pinfunction "2_2") (pintype "passive"))
      (node (ref "U$1") (pin "2") (pinfunction "G2(N)_2") (pintype "bidirectional"))
      (node (ref "U5") (pin "12") (pinfunction "PB0(ICP)_12") (pintype "bidirectional"))
    )
    (net (code "52") (name "SS") (class "Default")
      (node (ref "JP2") (pin "1") (pinfunction "1_1") (pintype "passive"))
      (node (ref "U$3") (pin "24") (pinfunction "CE0_24") (pintype "output"))
      (node (ref "U5") (pin "14") (pinfunction "PB2(SS/OC1B)_14") (pintype "bidirectional"))
    )
    (net (code "53") (name "TXO") (class "Default")
      (node (ref "U2") (pin "1") (pinfunction "TXD_1") (pintype "output"))
      (node (ref "U5") (pin "30") (pinfunction "PD0(RXD)_30") (pintype "bidirectional"))
    )
    (net (code "54") (name "unconnected-(U$3-CE1-Pad26)") (class "Default")
      (node (ref "U$3") (pin "26") (pinfunction "CE1_26") (pintype "output"))
    )
    (net (code "55") (name "unconnected-(U$3-GP4-Pad7)") (class "Default")
      (node (ref "U$3") (pin "7") (pinfunction "GP4_7") (pintype "bidirectional"))
    )
    (net (code "56") (name "unconnected-(U$3-GP17-Pad11)") (class "Default")
      (node (ref "U$3") (pin "11") (pinfunction "GP17_11") (pintype "bidirectional"))
    )
    (net (code "57") (name "unconnected-(U$3-GP18#-Pad12)") (class "Default")
      (node (ref "U$3") (pin "12") (pinfunction "GP18#_12") (pintype "bidirectional"))
    )
    (net (code "58") (name "unconnected-(U$3-GP19-Pad35)") (class "Default")
      (node (ref "U$3") (pin "35") (pinfunction "GP19_35") (pintype "bidirectional"))
    )
    (net (code "59") (name "unconnected-(U$3-GP20-Pad38)") (class "Default")
      (node (ref "U$3") (pin "38") (pinfunction "GP20_38") (pintype "bidirectional"))
    )
    (net (code "60") (name "unconnected-(U$3-GP21-Pad40)") (class "Default")
      (node (ref "U$3") (pin "40") (pinfunction "GP21_40") (pintype "bidirectional"))
    )
    (net (code "61") (name "unconnected-(U$3-GP22-Pad15)") (class "Default")
      (node (ref "U$3") (pin "15") (pinfunction "GP22_15") (pintype "bidirectional"))
    )
    (net (code "62") (name "unconnected-(U$3-GP23-Pad16)") (class "Default")
      (node (ref "U$3") (pin "16") (pinfunction "GP23_16") (pintype "bidirectional"))
    )
    (net (code "63") (name "unconnected-(U$3-GP24-Pad18)") (class "Default")
      (node (ref "U$3") (pin "18") (pinfunction "GP24_18") (pintype "bidirectional"))
    )
    (net (code "64") (name "unconnected-(U$3-GP25-Pad22)") (class "Default")
      (node (ref "U$3") (pin "22") (pinfunction "GP25_22") (pintype "bidirectional"))
    )
    (net (code "65") (name "unconnected-(U$3-GP26-Pad37)") (class "Default")
      (node (ref "U$3") (pin "37") (pinfunction "GP26_37") (pintype "bidirectional"))
    )
    (net (code "66") (name "unconnected-(U$3-GP27-Pad13)") (class "Default")
      (node (ref "U$3") (pin "13") (pinfunction "GP27_13") (pintype "bidirectional"))
    )
    (net (code "67") (name "unconnected-(U$3-ID_SC-Pad28)") (class "Default")
      (node (ref "U$3") (pin "28") (pinfunction "ID_SC_28") (pintype "bidirectional"))
    )
    (net (code "68") (name "unconnected-(U$3-ID_SD-Pad27)") (class "Default")
      (node (ref "U$3") (pin "27") (pinfunction "ID_SD_27") (pintype "bidirectional"))
    )
    (net (code "69") (name "unconnected-(U$3-RXI-Pad10)") (class "Default")
      (node (ref "U$3") (pin "10") (pinfunction "RXI_10") (pintype "input"))
    )
    (net (code "70") (name "unconnected-(U$3-SCL-Pad5)") (class "Default")
      (node (ref "U$3") (pin "5") (pinfunction "SCL_5") (pintype "bidirectional"))
    )
    (net (code "71") (name "unconnected-(U$3-SDA-Pad3)") (class "Default")
      (node (ref "U$3") (pin "3") (pinfunction "SDA_3") (pintype "bidirectional"))
    )
    (net (code "72") (name "unconnected-(U$3-TXO-Pad8)") (class "Default")
      (node (ref "U$3") (pin "8") (pinfunction "TXO_8") (pintype "output"))
    )
    (net (code "73") (name "unconnected-(U2-CTS-Pad11)") (class "Default")
      (node (ref "U2") (pin "11") (pinfunction "CTS_11") (pintype "input"))
    )
    (net (code "74") (name "unconnected-(U2-DCD-Pad10)") (class "Default")
      (node (ref "U2") (pin "10") (pinfunction "DCD_10") (pintype "input"))
    )
    (net (code "75") (name "unconnected-(U2-DSR-Pad9)") (class "Default")
      (node (ref "U2") (pin "9") (pinfunction "DSR_9") (pintype "input"))
    )
    (net (code "76") (name "unconnected-(U2-DTR-Pad2)") (class "Default")
      (node (ref "U2") (pin "2") (pinfunction "DTR_2") (pintype "output"))
    )
    (net (code "77") (name "unconnected-(U2-OSCI-Pad27)") (class "Default")
      (node (ref "U2") (pin "27") (pinfunction "OSCI_27") (pintype "input"))
    )
    (net (code "78") (name "unconnected-(U2-OSCO-Pad28)") (class "Default")
      (node (ref "U2") (pin "28") (pinfunction "OSCO_28") (pintype "output"))
    )
    (net (code "79") (name "unconnected-(U2-PWREN-Pad14)") (class "Default")
      (node (ref "U2") (pin "14") (pinfunction "PWREN_14") (pintype "input"))
    )
    (net (code "80") (name "unconnected-(U2-RESET-Pad19)") (class "Default")
      (node (ref "U2") (pin "19") (pinfunction "RESET_19") (pintype "input"))
    )
    (net (code "81") (name "unconnected-(U2-RI-Pad6)") (class "Default")
      (node (ref "U2") (pin "6") (pinfunction "RI_6") (pintype "input"))
    )
    (net (code "82") (name "unconnected-(U2-RTS-Pad3)") (class "Default")
      (node (ref "U2") (pin "3") (pinfunction "RTS_3") (pintype "output"))
    )
    (net (code "83") (name "unconnected-(U2-SLEEP-Pad12)") (class "Default")
      (node (ref "U2") (pin "12") (pinfunction "SLEEP_12") (pintype "input"))
    )
    (net (code "84") (name "unconnected-(U2-TXDEN-Pad13)") (class "Default")
      (node (ref "U2") (pin "13") (pinfunction "TXDEN_13") (pintype "input"))
    )
    (net (code "85") (name "unconnected-(U3-NC-Pad3)") (class "Default")
      (node (ref "U3") (pin "3") (pinfunction "NC_3") (pintype "bidirectional"))
    )
    (net (code "86") (name "unconnected-(U3-NC-Pad10)") (class "Default")
      (node (ref "U3") (pin "10") (pinfunction "NC_10") (pintype "bidirectional"))
    )
    (net (code "87") (name "unconnected-(U3-NC-Pad11)") (class "Default")
      (node (ref "U3") (pin "11") (pinfunction "NC_11") (pintype "bidirectional"))
    )
    (net (code "88") (name "unconnected-(U5-ADC6-Pad19)") (class "Default")
      (node (ref "U5") (pin "19") (pinfunction "ADC6_19") (pintype "bidirectional"))
    )
    (net (code "89") (name "unconnected-(U5-ADC7-Pad22)") (class "Default")
      (node (ref "U5") (pin "22") (pinfunction "ADC7_22") (pintype "bidirectional"))
    )
    (net (code "90") (name "unconnected-(U5-AREF-Pad20)") (class "Default")
      (node (ref "U5") (pin "20") (pinfunction "AREF_20") (pintype "bidirectional"))
    )
    (net (code "91") (name "unconnected-(U5-PC3(ADC3)-Pad26)") (class "Default")
      (node (ref "U5") (pin "26") (pinfunction "PC3(ADC3)_26") (pintype "bidirectional"))
    )
    (net (code "92") (name "unconnected-(U5-PD2(INT0)-Pad32)") (class "Default")
      (node (ref "U5") (pin "32") (pinfunction "PD2(INT0)_32") (pintype "bidirectional"))
    )
    (net (code "93") (name "unconnected-(U5-PD3(INT1)-Pad1)") (class "Default")
      (node (ref "U5") (pin "1") (pinfunction "PD3(INT1)_1") (pintype "bidirectional"))
    )
    (net (code "94") (name "unconnected-(U5-PD4(XCK{slash}T0)-Pad2)") (class "Default")
      (node (ref "U5") (pin "2") (pinfunction "PD4(XCK/T0)_2") (pintype "bidirectional"))
    )
  )
)
